# lamloei_node32s3wroom_cp2102_10_4layers.net
KiCad netlist of a schematic drawn in EAGLE
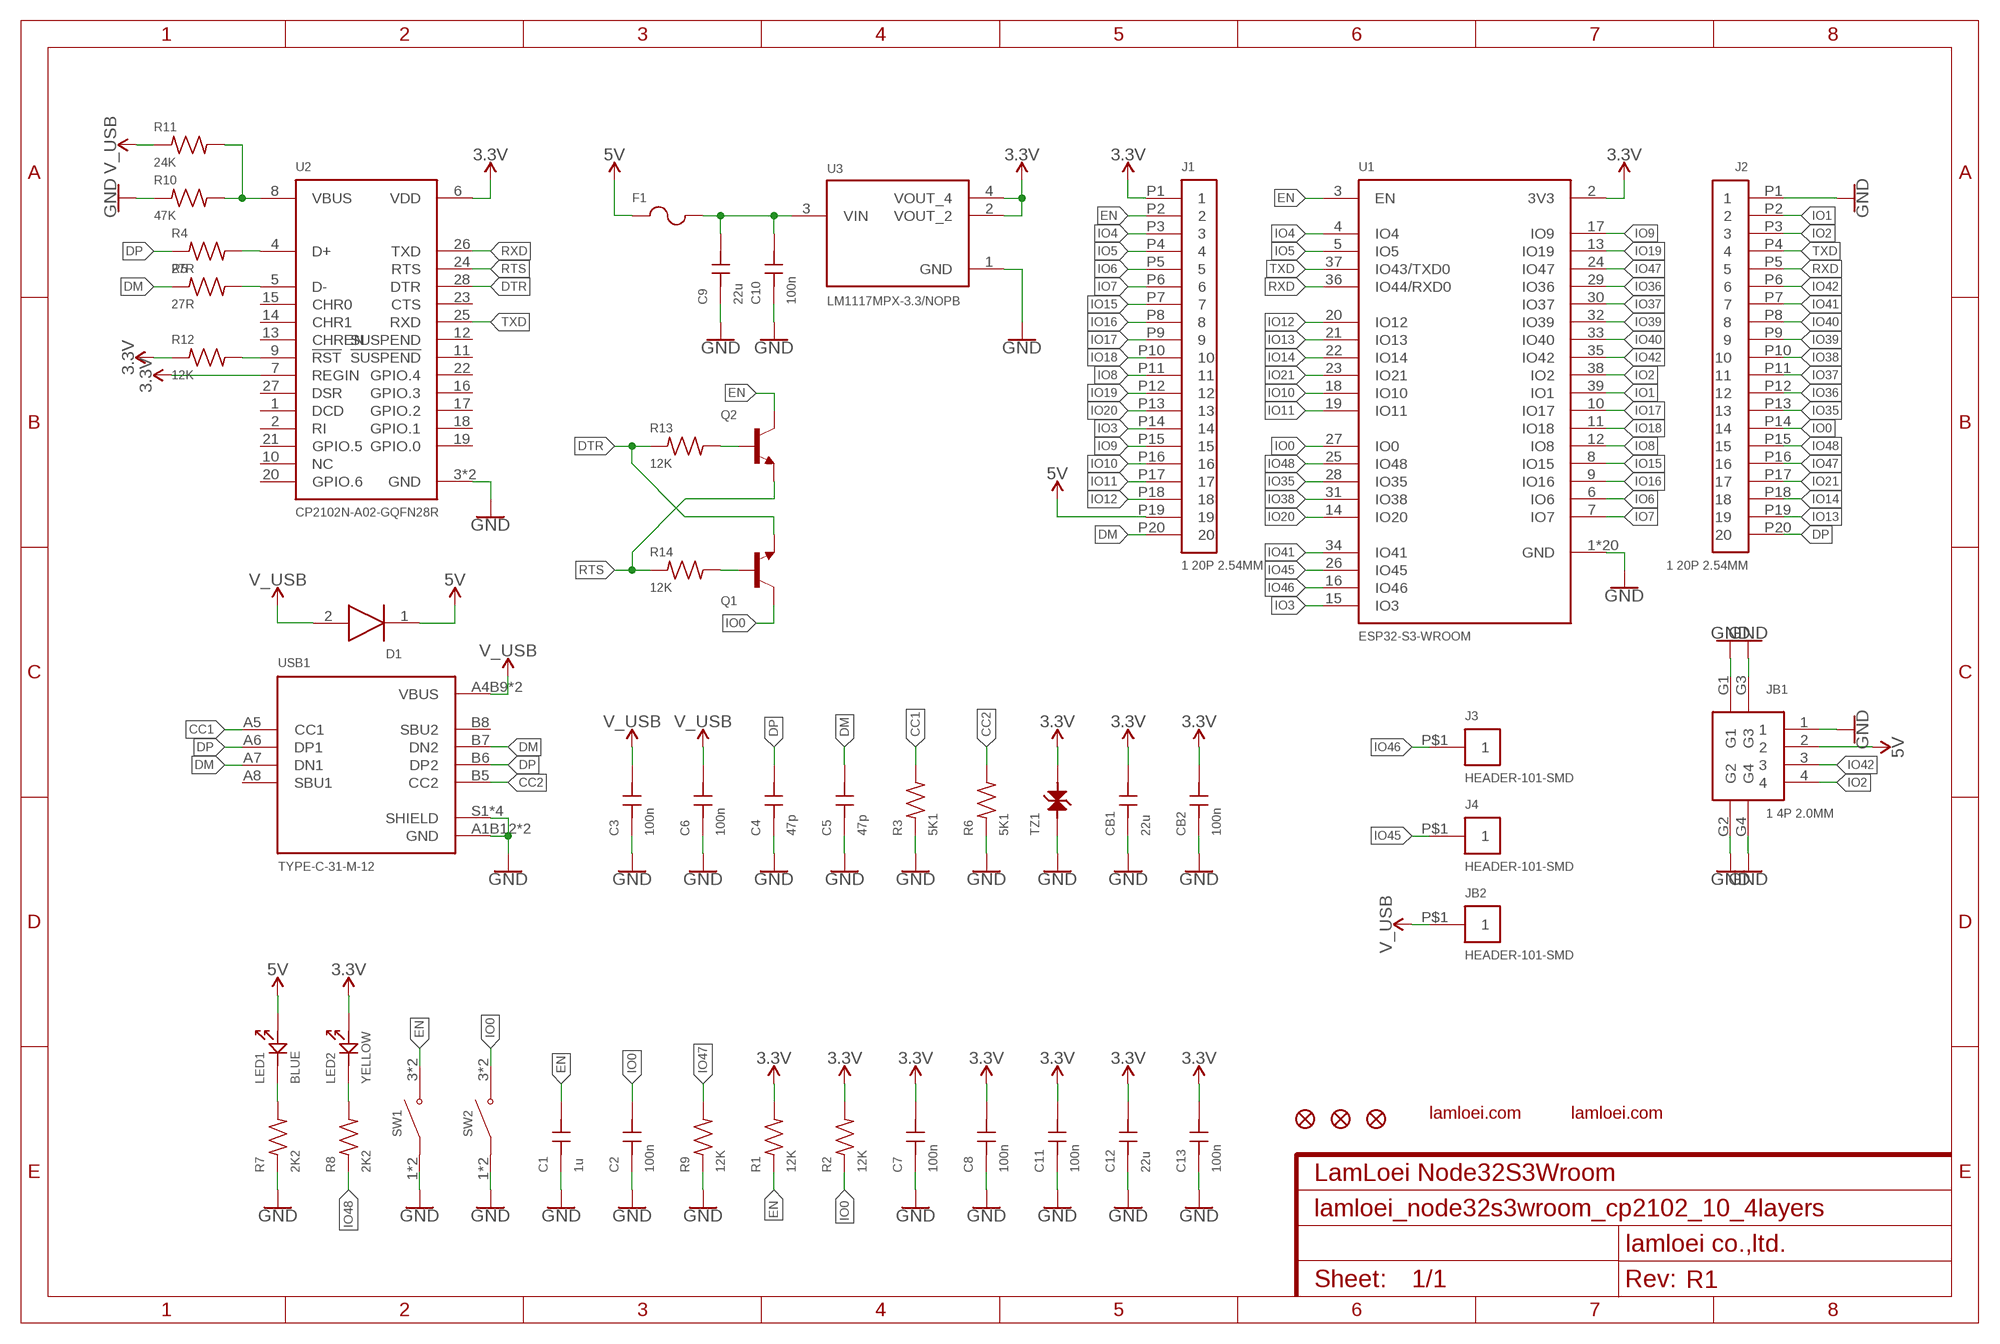
[diagram p0: schematic, sheet 1]

(export (version "E")
  (design (tool "Eeschema 10.0.6"))
  (components
    (comp (ref "C1")
      (value "1u")
      (footprint "eagle-import:GRM155R70J105KA12D")
      (fields (field (name "MANUFACTURER_PART_NUMBER") "GRM155R70J105KA12D"))
      (libsource (lib "eagle-import") (part "GRM155R70J105KA12D"))
    )
    (comp (ref "C2")
      (value "100n")
      (footprint "eagle-import:GCM155R71H104KE02D")
      (fields (field (name "MANUFACTURER_PART_NUMBER") "GCM155R71H104KE02D"))
      (libsource (lib "eagle-import") (part "GCM155R71H104KE02D"))
    )
    (comp (ref "C3")
      (value "100n")
      (footprint "eagle-import:GCM155R71H104KE02D")
      (fields (field (name "MANUFACTURER_PART_NUMBER") "GCM155R71H104KE02D"))
      (libsource (lib "eagle-import") (part "GCM155R71H104KE02D"))
    )
    (comp (ref "C4")
      (value "47p")
      (footprint "eagle-import:GCM1555C1H470JA16D")
      (fields (field (name "MANUFACTURER_PART_NUMBER") "GCM1555C1H470JA16D"))
      (libsource (lib "eagle-import") (part "GCM1555C1H470JA16D"))
    )
    (comp (ref "C5")
      (value "47p")
      (footprint "eagle-import:GCM1555C1H470JA16D")
      (fields (field (name "MANUFACTURER_PART_NUMBER") "GCM1555C1H470JA16D"))
      (libsource (lib "eagle-import") (part "GCM1555C1H470JA16D"))
    )
    (comp (ref "C6")
      (value "100n")
      (footprint "eagle-import:GCM155R71H104KE02D")
      (fields (field (name "MANUFACTURER_PART_NUMBER") "GCM155R71H104KE02D"))
      (libsource (lib "eagle-import") (part "GCM155R71H104KE02D"))
    )
    (comp (ref "C7")
      (value "100n")
      (footprint "eagle-import:GCM155R71H104KE02D")
      (fields (field (name "MANUFACTURER_PART_NUMBER") "GCM155R71H104KE02D"))
      (libsource (lib "eagle-import") (part "GCM155R71H104KE02D"))
    )
    (comp (ref "C8")
      (value "100n")
      (footprint "eagle-import:GCM155R71H104KE02D")
      (fields (field (name "MANUFACTURER_PART_NUMBER") "GCM155R71H104KE02D"))
      (libsource (lib "eagle-import") (part "GCM155R71H104KE02D"))
    )
    (comp (ref "C9")
      (value "22u")
      (footprint "eagle-import:GCM21BR71H105KA03L")
      (fields (field (name "MANUFACTURER_PART_NUMBER") "GCM21BR71H105KA03L"))
      (libsource (lib "eagle-import") (part "GCM21BR71H105KA03L"))
    )
    (comp (ref "C10")
      (value "100n")
      (footprint "eagle-import:GCM155R71H104KE02D")
      (fields (field (name "MANUFACTURER_PART_NUMBER") "GCM155R71H104KE02D"))
      (libsource (lib "eagle-import") (part "GCM155R71H104KE02D"))
    )
    (comp (ref "C11")
      (value "100n")
      (footprint "eagle-import:GCM155R71H104KE02D")
      (fields (field (name "MANUFACTURER_PART_NUMBER") "GCM155R71H104KE02D"))
      (libsource (lib "eagle-import") (part "GCM155R71H104KE02D"))
    )
    (comp (ref "C12")
      (value "22u")
      (footprint "eagle-import:GCM21BR71H105KA03L")
      (fields (field (name "MANUFACTURER_PART_NUMBER") "GCM21BR71H105KA03L"))
      (libsource (lib "eagle-import") (part "GCM21BR71H105KA03L"))
    )
    (comp (ref "C13")
      (value "100n")
      (footprint "eagle-import:GCM155R71H104KE02D")
      (fields (field (name "MANUFACTURER_PART_NUMBER") "GCM155R71H104KE02D"))
      (libsource (lib "eagle-import") (part "GCM155R71H104KE02D"))
    )
    (comp (ref "CB1")
      (value "22u")
      (footprint "eagle-import:GCM21BR71H105KA03L")
      (fields (field (name "MANUFACTURER_PART_NUMBER") "GCM21BR71H105KA03L"))
      (libsource (lib "eagle-import") (part "GCM21BR71H105KA03L"))
    )
    (comp (ref "CB2")
      (value "100n")
      (footprint "eagle-import:GCM155R71H104KE02D")
      (fields (field (name "MANUFACTURER_PART_NUMBER") "GCM155R71H104KE02D"))
      (libsource (lib "eagle-import") (part "GCM155R71H104KE02D"))
    )
    (comp (ref "D1")
      (value "PMEG4050EP,115")
      (footprint "eagle-import:PMEG4050EP,115")
      (fields (field (name "RS_PART_NUMBER") "7805405P"))
      (libsource (lib "eagle-import") (part "PMEG4050EP,115"))
    )
    (comp (ref "F1")
      (value "MF-NSMF050-2")
      (footprint "eagle-import:MF-NSMF050-2")
      (fields (field (name "LCSC_PART") "C75464") (field (name "MANUFACTURER") "BOURNS"))
      (libsource (lib "eagle-import") (part "MF-NSMF050-2"))
    )
    (comp (ref "J1")
      (value "1 20P 2.54MM")
      (footprint "eagle-import:HEADER-120")
      (libsource (lib "eagle-import") (part "HEADER-120"))
    )
    (comp (ref "J2")
      (value "1 20P 2.54MM")
      (footprint "eagle-import:HEADER-120")
      (libsource (lib "eagle-import") (part "lamloei_e77_HEADER-120B_HEADER-120"))
    )
    (comp (ref "J3")
      (value "HEADER-101-SMD")
      (footprint "eagle-import:HEADER-101-SMD")
      (libsource (lib "eagle-import") (part "HEADER-101-SMD"))
    )
    (comp (ref "J4")
      (value "HEADER-101-SMD")
      (footprint "eagle-import:HEADER-101-SMD")
      (libsource (lib "eagle-import") (part "HEADER-101-SMD"))
    )
    (comp (ref "JB1")
      (value "1 4P 2.0MM")
      (footprint "eagle-import:A2012WR-S-4P")
      (libsource (lib "eagle-import") (part "A2012WR-S-4P"))
    )
    (comp (ref "JB2")
      (value "HEADER-101-SMD")
      (footprint "eagle-import:HEADER-101-SMD")
      (libsource (lib "eagle-import") (part "HEADER-101-SMD"))
    )
    (comp (ref "LED1")
      (value "BLUE")
      (footprint "eagle-import:19-217BHC-ZL1M2RY3T")
      (fields (field (name "MANUFACTURER_PART_NUMBER") "19-217BHC-ZL1M2RY3T"))
      (libsource (lib "eagle-import") (part "19-217BHC-ZL1M2RY3T"))
    )
    (comp (ref "LED2")
      (value "YELLOW")
      (footprint "eagle-import:19-213_Y2C-CQ2R2L_3T(CY)")
      (fields (field (name "MANUFACTURER_PART_NUMBER") "19-213/Y2C-CQ2R2L/3T(CY)"))
      (libsource (lib "eagle-import") (part "19-213/Y2C-CQ2R2L/3T(CY)"))
    )
    (comp (ref "Q1")
      (value "BC847B,215")
      (footprint "eagle-import:BC847B,215")
      (fields (field (name "MF") "ON Semiconductor") (field (name "MP") "BC847BLT3G"))
      (libsource (lib "eagle-import") (part "BC847B,215"))
    )
    (comp (ref "Q2")
      (value "BC847B,215")
      (footprint "eagle-import:BC847B,215")
      (fields (field (name "MF") "ON Semiconductor") (field (name "MP") "BC847BLT3G"))
      (libsource (lib "eagle-import") (part "BC847B,215"))
    )
    (comp (ref "R1")
      (value "12K")
      (footprint "eagle-import:R0402")
      (fields
        (field (name "LCSC_PART") "C114760")
        (field (name "MANUFACTURER") "YAGEO")
        (field (name "MANUFACTURER_PART_NUMBER") "RC0402FR-0712KL")
      )
      (libsource (lib "eagle-import") (part "RC0402FR-0712KL"))
    )
    (comp (ref "R2")
      (value "12K")
      (footprint "eagle-import:R0402")
      (fields
        (field (name "LCSC_PART") "C114760")
        (field (name "MANUFACTURER") "YAGEO")
        (field (name "MANUFACTURER_PART_NUMBER") "RC0402FR-0712KL")
      )
      (libsource (lib "eagle-import") (part "RC0402FR-0712KL"))
    )
    (comp (ref "R3")
      (value "5K1")
      (footprint "eagle-import:R0402")
      (fields
        (field (name "LCSC_PART") "C105872")
        (field (name "MANUFACTURER") "YAGEO")
        (field (name "MANUFACTURER_PART_NUMBER") "RC0402FR-075K1L")
      )
      (libsource (lib "eagle-import") (part "RC0402FR-075K1L"))
    )
    (comp (ref "R4")
      (value "27R")
      (footprint "eagle-import:R0402")
      (fields
        (field (name "LCSC_PART") "C138021")
        (field (name "MANUFACTURER") "YAGEO")
        (field (name "MANUFACTURER_PART_NUMBER") "RC0402FR-0727RL")
      )
      (libsource (lib "eagle-import") (part "RC0402FR-0727RL"))
    )
    (comp (ref "R5")
      (value "27R")
      (footprint "eagle-import:R0402")
      (fields
        (field (name "LCSC_PART") "C138021")
        (field (name "MANUFACTURER") "YAGEO")
        (field (name "MANUFACTURER_PART_NUMBER") "RC0402FR-0727RL")
      )
      (libsource (lib "eagle-import") (part "RC0402FR-0727RL"))
    )
    (comp (ref "R6")
      (value "5K1")
      (footprint "eagle-import:R0402")
      (fields
        (field (name "LCSC_PART") "C105872")
        (field (name "MANUFACTURER") "YAGEO")
        (field (name "MANUFACTURER_PART_NUMBER") "RC0402FR-075K1L")
      )
      (libsource (lib "eagle-import") (part "RC0402FR-075K1L"))
    )
    (comp (ref "R7")
      (value "2K2")
      (footprint "eagle-import:R0402")
      (fields
        (field (name "LCSC_PART") "C114762")
        (field (name "MANUFACTURER") "YAGEO")
        (field (name "MANUFACTURER_PART_NUMBER") "RC0402FR-072K2L")
      )
      (libsource (lib "eagle-import") (part "RC0402FR-072K2L"))
    )
    (comp (ref "R8")
      (value "2K2")
      (footprint "eagle-import:R0402")
      (fields
        (field (name "LCSC_PART") "C114762")
        (field (name "MANUFACTURER") "YAGEO")
        (field (name "MANUFACTURER_PART_NUMBER") "RC0402FR-072K2L")
      )
      (libsource (lib "eagle-import") (part "RC0402FR-072K2L"))
    )
    (comp (ref "R9")
      (value "12K")
      (footprint "eagle-import:R0402")
      (fields
        (field (name "LCSC_PART") "C114760")
        (field (name "MANUFACTURER") "YAGEO")
        (field (name "MANUFACTURER_PART_NUMBER") "RC0402FR-0712KL")
      )
      (libsource (lib "eagle-import") (part "RC0402FR-0712KL"))
    )
    (comp (ref "R10")
      (value "47K")
      (footprint "eagle-import:R0402")
      (fields
        (field (name "LCSC_PART") "C93943")
        (field (name "MANUFACTURER") "YAGEO")
        (field (name "MANUFACTURER_PART_NUMBER") "RC0402FR-0747KL")
      )
      (libsource (lib "eagle-import") (part "RC0402FR-0747KL"))
    )
    (comp (ref "R11")
      (value "24K")
      (footprint "eagle-import:R0402")
      (fields
        (field (name "LCSC_PART") "C138026")
        (field (name "MANUFACTURER") "YAGEO")
        (field (name "MANUFACTURER_PART_NUMBER") "RC0402FR-0724KL")
      )
      (libsource (lib "eagle-import") (part "RC0402FR-0724KL"))
    )
    (comp (ref "R12")
      (value "12K")
      (footprint "eagle-import:R0402")
      (fields
        (field (name "LCSC_PART") "C114760")
        (field (name "MANUFACTURER") "YAGEO")
        (field (name "MANUFACTURER_PART_NUMBER") "RC0402FR-0712KL")
      )
      (libsource (lib "eagle-import") (part "RC0402FR-0712KL"))
    )
    (comp (ref "R13")
      (value "12K")
      (footprint "eagle-import:R0402")
      (fields
        (field (name "LCSC_PART") "C114760")
        (field (name "MANUFACTURER") "YAGEO")
        (field (name "MANUFACTURER_PART_NUMBER") "RC0402FR-0712KL")
      )
      (libsource (lib "eagle-import") (part "RC0402FR-0712KL"))
    )
    (comp (ref "R14")
      (value "12K")
      (footprint "eagle-import:R0402")
      (fields
        (field (name "LCSC_PART") "C114760")
        (field (name "MANUFACTURER") "YAGEO")
        (field (name "MANUFACTURER_PART_NUMBER") "RC0402FR-0712KL")
      )
      (libsource (lib "eagle-import") (part "RC0402FR-0712KL"))
    )
    (comp (ref "SW1")
      (value "K2-1808SN-A4SW-01")
      (footprint "eagle-import:K2-1808SN-A4SW-01")
      (fields (field (name "COMMENT") "4-1437565-2") (field (name "MF") "TE Connectivity"))
      (libsource (lib "eagle-import") (part "K2-1808SN-A4SW-01"))
    )
    (comp (ref "SW2")
      (value "K2-1808SN-A4SW-01")
      (footprint "eagle-import:K2-1808SN-A4SW-01")
      (fields (field (name "COMMENT") "4-1437565-2") (field (name "MF") "TE Connectivity"))
      (libsource (lib "eagle-import") (part "K2-1808SN-A4SW-01"))
    )
    (comp (ref "TZ1")
      (value "LXES15AAA1-153")
      (footprint "eagle-import:LXES15AAA1-153")
      (fields (field (name "LCSC_PART") "C86141") (field (name "MANUFACTURER") "Murata"))
      (libsource (lib "eagle-import") (part "LXES15AAA1-153"))
    )
    (comp (ref "U1")
      (value "ESP32-S3-WROOM")
      (footprint "eagle-import:ESP32-S3-WROOM")
      (fields (field (name "MF") "Olimex LTD") (field (name "MP") "ESP-WROOM-32"))
      (libsource (lib "eagle-import") (part "ESP32-S3-WROOM"))
    )
    (comp (ref "U2")
      (value "CP2102N-A02-GQFN28R")
      (footprint "eagle-import:CP2102N-A02-GQFN28R")
      (libsource (lib "eagle-import") (part "CP2102N-A02-GQFN28R"))
    )
    (comp (ref "U3")
      (value "LM1117MPX-3.3/NOPB")
      (footprint "eagle-import:LM1117MPX-3.3_NOPB")
      (fields (field (name "MF") "Texas Instruments"))
      (libsource (lib "eagle-import") (part "LM1117MPX-3.3/NOPB"))
    )
    (comp (ref "USB1")
      (value "TYPE-C-31-M-12")
      (footprint "eagle-import:TYPE-C-31-M-12")
      (fields (field (name "MF") "HRO Electronics Co., Ltd."))
      (libsource (lib "eagle-import") (part "TYPE-C-31-M-12"))
    )
    (comp (ref "ZFD1")
      (value "FIDUCIAL1X2")
      (footprint "eagle-import:FIDUCIAL-1X2")
      (libsource (lib "eagle-import") (part "FIDUCIAL1X2"))
    )
    (comp (ref "ZFD2")
      (value "FIDUCIAL1X2")
      (footprint "eagle-import:FIDUCIAL-1X2")
      (libsource (lib "eagle-import") (part "FIDUCIAL1X2"))
    )
    (comp (ref "ZFD3")
      (value "FIDUCIAL1X2")
      (footprint "eagle-import:FIDUCIAL-1X2")
      (libsource (lib "eagle-import") (part "FIDUCIAL1X2"))
    )
    (comp (ref "ZL1")
      (value "LAMLEOI_LOGO_3")
      (footprint "eagle-import:LAMLEOI_LOGO_3")
      (libsource (lib "eagle-import") (part "LAMLEOI_LOGO_3"))
    )
    (comp (ref "ZL2")
      (value "LAMLEOI_LOGO_3")
      (footprint "eagle-import:LAMLEOI_LOGO_3")
      (libsource (lib "eagle-import") (part "LAMLEOI_LOGO_3"))
    )
  )
  (nets
    (net (code "1") (name "/GPIO.5") (class "Default")
      (node (ref "U2") (pin "21") (pinfunction "GPIO.5_21") (pintype "power_in"))
    )
    (net (code "2") (name "3.3V") (class "Default")
      (node (ref "C11") (pin "2") (pinfunction "2_2") (pintype "passive"))
      (node (ref "C12") (pin "2") (pinfunction "2_2") (pintype "passive"))
      (node (ref "C13") (pin "2") (pinfunction "2_2") (pintype "passive"))
      (node (ref "C7") (pin "2") (pinfunction "2_2") (pintype "passive"))
      (node (ref "C8") (pin "2") (pinfunction "2_2") (pintype "passive"))
      (node (ref "CB1") (pin "2") (pinfunction "2_2") (pintype "passive"))
      (node (ref "CB2") (pin "2") (pinfunction "2_2") (pintype "passive"))
      (node (ref "J1") (pin "P1") (pinfunction "1_P1") (pintype "passive"))
      (node (ref "LED2") (pin "2") (pinfunction "2_2") (pintype "passive"))
      (node (ref "R1") (pin "2") (pinfunction "2_2") (pintype "passive"))
      (node (ref "R12") (pin "1") (pinfunction "1_1") (pintype "passive"))
      (node (ref "R2") (pin "2") (pinfunction "2_2") (pintype "passive"))
      (node (ref "TZ1") (pin "2") (pinfunction "2_2") (pintype "passive"))
      (node (ref "U1") (pin "2") (pinfunction "3V3_2") (pintype "power_in"))
      (node (ref "U2") (pin "6") (pinfunction "VDD_6") (pintype "power_in"))
      (node (ref "U2") (pin "7") (pinfunction "REGIN_7") (pintype "input"))
      (node (ref "U3") (pin "2") (pinfunction "VOUT_2_2") (pintype "output"))
      (node (ref "U3") (pin "4") (pinfunction "VOUT_4_4") (pintype "output"))
    )
    (net (code "3") (name "5V") (class "Default")
      (node (ref "D1") (pin "1") (pinfunction "K_1") (pintype "bidirectional"))
      (node (ref "F1") (pin "1") (pinfunction "1_1") (pintype "passive"))
      (node (ref "J1") (pin "P19") (pinfunction "19_P19") (pintype "passive"))
      (node (ref "JB1") (pin "2") (pinfunction "2_2") (pintype "bidirectional"))
      (node (ref "LED1") (pin "2") (pinfunction "2_2") (pintype "passive"))
    )
    (net (code "4") (name "CC1") (class "Default")
      (node (ref "R3") (pin "2") (pinfunction "2_2") (pintype "passive"))
      (node (ref "USB1") (pin "A5") (pinfunction "CC1_A5") (pintype "bidirectional"))
    )
    (net (code "5") (name "CC2") (class "Default")
      (node (ref "R6") (pin "2") (pinfunction "2_2") (pintype "passive"))
      (node (ref "USB1") (pin "B5") (pinfunction "CC2_B5") (pintype "bidirectional"))
    )
    (net (code "6") (name "DM") (class "Default")
      (node (ref "C5") (pin "2") (pinfunction "2_2") (pintype "passive"))
      (node (ref "J1") (pin "P20") (pinfunction "20_P20") (pintype "passive"))
      (node (ref "R5") (pin "1") (pinfunction "1_1") (pintype "passive"))
      (node (ref "USB1") (pin "A7") (pinfunction "DN1_A7") (pintype "bidirectional"))
      (node (ref "USB1") (pin "B7") (pinfunction "DN2_B7") (pintype "bidirectional"))
    )
    (net (code "7") (name "DP") (class "Default")
      (node (ref "C4") (pin "2") (pinfunction "2_2") (pintype "passive"))
      (node (ref "J2") (pin "P20") (pinfunction "20_P20") (pintype "passive"))
      (node (ref "R4") (pin "1") (pinfunction "1_1") (pintype "passive"))
      (node (ref "USB1") (pin "A6") (pinfunction "DP1_A6") (pintype "bidirectional"))
      (node (ref "USB1") (pin "B6") (pinfunction "DP2_B6") (pintype "bidirectional"))
    )
    (net (code "8") (name "DTR") (class "Default")
      (node (ref "Q1") (pin "E") (pinfunction "E_E") (pintype "passive"))
      (node (ref "R13") (pin "1") (pinfunction "1_1") (pintype "passive"))
      (node (ref "U2") (pin "28") (pinfunction "DTR_28") (pintype "output"))
    )
    (net (code "9") (name "EN") (class "Default")
      (node (ref "C1") (pin "2") (pinfunction "2_2") (pintype "passive"))
      (node (ref "J1") (pin "P2") (pinfunction "2_P2") (pintype "passive"))
      (node (ref "Q2") (pin "C") (pinfunction "C_C") (pintype "passive"))
      (node (ref "R1") (pin "1") (pinfunction "1_1") (pintype "passive"))
      (node (ref "SW1") (pin "3") (pinfunction "NO_3") (pintype "passive"))
      (node (ref "SW1") (pin "4") (pinfunction "NO_4") (pintype "passive"))
      (node (ref "U1") (pin "3") (pinfunction "EN_3") (pintype "input"))
    )
    (net (code "10") (name "GND") (class "Default")
      (node (ref "C1") (pin "1") (pinfunction "1_1") (pintype "passive"))
      (node (ref "C10") (pin "1") (pinfunction "1_1") (pintype "passive"))
      (node (ref "C11") (pin "1") (pinfunction "1_1") (pintype "passive"))
      (node (ref "C12") (pin "1") (pinfunction "1_1") (pintype "passive"))
      (node (ref "C13") (pin "1") (pinfunction "1_1") (pintype "passive"))
      (node (ref "C2") (pin "1") (pinfunction "1_1") (pintype "passive"))
      (node (ref "C3") (pin "1") (pinfunction "1_1") (pintype "passive"))
      (node (ref "C4") (pin "1") (pinfunction "1_1") (pintype "passive"))
      (node (ref "C5") (pin "1") (pinfunction "1_1") (pintype "passive"))
      (node (ref "C6") (pin "1") (pinfunction "1_1") (pintype "passive"))
      (node (ref "C7") (pin "1") (pinfunction "1_1") (pintype "passive"))
      (node (ref "C8") (pin "1") (pinfunction "1_1") (pintype "passive"))
      (node (ref "C9") (pin "1") (pinfunction "1_1") (pintype "passive"))
      (node (ref "CB1") (pin "1") (pinfunction "1_1") (pintype "passive"))
      (node (ref "CB2") (pin "1") (pinfunction "1_1") (pintype "passive"))
      (node (ref "J2") (pin "P1") (pinfunction "1_P1") (pintype "passive"))
      (node (ref "JB1") (pin "1") (pinfunction "1_1") (pintype "bidirectional"))
      (node (ref "JB1") (pin "G1") (pinfunction "G1_G1") (pintype "bidirectional"))
      (node (ref "JB1") (pin "G2") (pinfunction "G2_G2") (pintype "bidirectional"))
      (node (ref "JB1") (pin "G3") (pinfunction "G3_G3") (pintype "bidirectional"))
      (node (ref "JB1") (pin "G4") (pinfunction "G4_G4") (pintype "bidirectional"))
      (node (ref "R10") (pin "1") (pinfunction "1_1") (pintype "passive"))
      (node (ref "R3") (pin "1") (pinfunction "1_1") (pintype "passive"))
      (node (ref "R6") (pin "1") (pinfunction "1_1") (pintype "passive"))
      (node (ref "R7") (pin "1") (pinfunction "1_1") (pintype "passive"))
      (node (ref "R9") (pin "1") (pinfunction "1_1") (pintype "passive"))
      (node (ref "SW1") (pin "1") (pinfunction "COM_1") (pintype "passive"))
      (node (ref "SW1") (pin "2") (pinfunction "COM_2") (pintype "passive"))
      (node (ref "SW2") (pin "1") (pinfunction "COM_1") (pintype "passive"))
      (node (ref "SW2") (pin "2") (pinfunction "COM_2") (pintype "passive"))
      (node (ref "TZ1") (pin "1") (pinfunction "1_1") (pintype "passive"))
      (node (ref "U1") (pin "1") (pinfunction "GND_1") (pintype "power_in"))
      (node (ref "U1") (pin "1.1") (pinfunction "GND_1.1") (pintype "power_in"))
      (node (ref "U1") (pin "1.10") (pinfunction "GND_1.10") (pintype "power_in"))
      (node (ref "U1") (pin "1.11") (pinfunction "GND_1.11") (pintype "power_in"))
      (node (ref "U1") (pin "1.12") (pinfunction "GND_1.12") (pintype "power_in"))
      (node (ref "U1") (pin "1.13") (pinfunction "GND_1.13") (pintype "power_in"))
      (node (ref "U1") (pin "1.14") (pinfunction "GND_1.14") (pintype "power_in"))
      (node (ref "U1") (pin "1.15") (pinfunction "GND_1.15") (pintype "power_in"))
      (node (ref "U1") (pin "1.16") (pinfunction "GND_1.16") (pintype "power_in"))
      (node (ref "U1") (pin "1.17") (pinfunction "GND_1.17") (pintype "power_in"))
      (node (ref "U1") (pin "1.18") (pinfunction "GND_1.18") (pintype "power_in"))
      (node (ref "U1") (pin "1.2") (pinfunction "GND_1.2") (pintype "power_in"))
      (node (ref "U1") (pin "1.3") (pinfunction "GND_1.3") (pintype "power_in"))
      (node (ref "U1") (pin "1.4") (pinfunction "GND_1.4") (pintype "power_in"))
      (node (ref "U1") (pin "1.5") (pinfunction "GND_1.5") (pintype "power_in"))
      (node (ref "U1") (pin "1.6") (pinfunction "GND_1.6") (pintype "power_in"))
      (node (ref "U1") (pin "1.7") (pinfunction "GND_1.7") (pintype "power_in"))
      (node (ref "U1") (pin "1.8") (pinfunction "GND_1.8") (pintype "power_in"))
      (node (ref "U1") (pin "1.9") (pinfunction "GND_1.9") (pintype "power_in"))
      (node (ref "U1") (pin "40") (pinfunction "GND_40") (pintype "power_in"))
      (node (ref "U2") (pin "29") (pinfunction "GND_29") (pintype "power_in"))
      (node (ref "U2") (pin "3") (pinfunction "GND_3") (pintype "power_in"))
      (node (ref "U3") (pin "1") (pinfunction "GND_1") (pintype "power_in"))
      (node (ref "USB1") (pin "A1B12") (pinfunction "GND_A1B12") (pintype "power_in"))
      (node (ref "USB1") (pin "B1A12") (pinfunction "GND_B1A12") (pintype "power_in"))
      (node (ref "USB1") (pin "S1") (pinfunction "SHIELD_S1") (pintype "passive"))
      (node (ref "USB1") (pin "S2") (pinfunction "SHIELD_S2") (pintype "passive"))
      (node (ref "USB1") (pin "S3") (pinfunction "SHIELD_S3") (pintype "passive"))
      (node (ref "USB1") (pin "S4") (pinfunction "SHIELD_S4") (pintype "passive"))
    )
    (net (code "11") (name "IO0") (class "Default")
      (node (ref "C2") (pin "2") (pinfunction "2_2") (pintype "passive"))
      (node (ref "J2") (pin "P14") (pinfunction "14_P14") (pintype "passive"))
      (node (ref "Q1") (pin "C") (pinfunction "C_C") (pintype "passive"))
      (node (ref "R2") (pin "1") (pinfunction "1_1") (pintype "passive"))
      (node (ref "SW2") (pin "3") (pinfunction "NO_3") (pintype "passive"))
      (node (ref "SW2") (pin "4") (pinfunction "NO_4") (pintype "passive"))
      (node (ref "U1") (pin "27") (pinfunction "IO0_27") (pintype "bidirectional"))
    )
    (net (code "12") (name "IO1") (class "Default")
      (node (ref "J2") (pin "P2") (pinfunction "2_P2") (pintype "passive"))
      (node (ref "U1") (pin "39") (pinfunction "IO1_39") (pintype "bidirectional"))
    )
    (net (code "13") (name "IO2") (class "Default")
      (node (ref "J2") (pin "P3") (pinfunction "3_P3") (pintype "passive"))
      (node (ref "JB1") (pin "4") (pinfunction "4_4") (pintype "bidirectional"))
      (node (ref "U1") (pin "38") (pinfunction "IO2_38") (pintype "bidirectional"))
    )
    (net (code "14") (name "IO3") (class "Default")
      (node (ref "J1") (pin "P14") (pinfunction "14_P14") (pintype "passive"))
      (node (ref "U1") (pin "15") (pinfunction "IO3_15") (pintype "bidirectional"))
    )
    (net (code "15") (name "IO4") (class "Default")
      (node (ref "J1") (pin "P3") (pinfunction "3_P3") (pintype "passive"))
      (node (ref "U1") (pin "4") (pinfunction "IO4_4") (pintype "input"))
    )
    (net (code "16") (name "IO5") (class "Default")
      (node (ref "J1") (pin "P4") (pinfunction "4_P4") (pintype "passive"))
      (node (ref "U1") (pin "5") (pinfunction "IO5_5") (pintype "input"))
    )
    (net (code "17") (name "IO6") (class "Default")
      (node (ref "J1") (pin "P5") (pinfunction "5_P5") (pintype "passive"))
      (node (ref "U1") (pin "6") (pinfunction "IO6_6") (pintype "bidirectional"))
    )
    (net (code "18") (name "IO7") (class "Default")
      (node (ref "J1") (pin "P6") (pinfunction "6_P6") (pintype "passive"))
      (node (ref "U1") (pin "7") (pinfunction "IO7_7") (pintype "bidirectional"))
    )
    (net (code "19") (name "IO8") (class "Default")
      (node (ref "J1") (pin "P11") (pinfunction "11_P11") (pintype "passive"))
      (node (ref "U1") (pin "12") (pinfunction "IO8_12") (pintype "bidirectional"))
    )
    (net (code "20") (name "IO9") (class "Default")
      (node (ref "J1") (pin "P15") (pinfunction "15_P15") (pintype "passive"))
      (node (ref "U1") (pin "17") (pinfunction "IO9_17") (pintype "bidirectional"))
    )
    (net (code "21") (name "IO10") (class "Default")
      (node (ref "J1") (pin "P16") (pinfunction "16_P16") (pintype "passive"))
      (node (ref "U1") (pin "18") (pinfunction "IO10_18") (pintype "bidirectional"))
    )
    (net (code "22") (name "IO11") (class "Default")
      (node (ref "J1") (pin "P17") (pinfunction "17_P17") (pintype "passive"))
      (node (ref "U1") (pin "19") (pinfunction "IO11_19") (pintype "bidirectional"))
    )
    (net (code "23") (name "IO12") (class "Default")
      (node (ref "J1") (pin "P18") (pinfunction "18_P18") (pintype "passive"))
      (node (ref "U1") (pin "20") (pinfunction "IO12_20") (pintype "bidirectional"))
    )
    (net (code "24") (name "IO13") (class "Default")
      (node (ref "J2") (pin "P19") (pinfunction "19_P19") (pintype "passive"))
      (node (ref "U1") (pin "21") (pinfunction "IO13_21") (pintype "bidirectional"))
    )
    (net (code "25") (name "IO14") (class "Default")
      (node (ref "J2") (pin "P18") (pinfunction "18_P18") (pintype "passive"))
      (node (ref "U1") (pin "22") (pinfunction "IO14_22") (pintype "bidirectional"))
    )
    (net (code "26") (name "IO15") (class "Default")
      (node (ref "J1") (pin "P7") (pinfunction "7_P7") (pintype "passive"))
      (node (ref "U1") (pin "8") (pinfunction "IO15_8") (pintype "bidirectional"))
    )
    (net (code "27") (name "IO16") (class "Default")
      (node (ref "J1") (pin "P8") (pinfunction "8_P8") (pintype "passive"))
      (node (ref "U1") (pin "9") (pinfunction "IO16_9") (pintype "bidirectional"))
    )
    (net (code "28") (name "IO17") (class "Default")
      (node (ref "J1") (pin "P9") (pinfunction "9_P9") (pintype "passive"))
      (node (ref "U1") (pin "10") (pinfunction "IO17_10") (pintype "bidirectional"))
    )
    (net (code "29") (name "IO18") (class "Default")
      (node (ref "J1") (pin "P10") (pinfunction "10_P10") (pintype "passive"))
      (node (ref "U1") (pin "11") (pinfunction "IO18_11") (pintype "bidirectional"))
    )
    (net (code "30") (name "IO19") (class "Default")
      (node (ref "J1") (pin "P12") (pinfunction "12_P12") (pintype "passive"))
      (node (ref "U1") (pin "13") (pinfunction "IO19_13") (pintype "bidirectional"))
    )
    (net (code "31") (name "IO20") (class "Default")
      (node (ref "J1") (pin "P13") (pinfunction "13_P13") (pintype "passive"))
      (node (ref "U1") (pin "14") (pinfunction "IO20_14") (pintype "bidirectional"))
    )
    (net (code "32") (name "IO21") (class "Default")
      (node (ref "J2") (pin "P17") (pinfunction "17_P17") (pintype "passive"))
      (node (ref "U1") (pin "23") (pinfunction "IO21_23") (pintype "bidirectional"))
    )
    (net (code "33") (name "IO35") (class "Default")
      (node (ref "J2") (pin "P13") (pinfunction "13_P13") (pintype "passive"))
      (node (ref "U1") (pin "28") (pinfunction "IO35_28") (pintype "bidirectional"))
    )
    (net (code "34") (name "IO36") (class "Default")
      (node (ref "J2") (pin "P12") (pinfunction "12_P12") (pintype "passive"))
      (node (ref "U1") (pin "29") (pinfunction "IO36_29") (pintype "bidirectional"))
    )
    (net (code "35") (name "IO37") (class "Default")
      (node (ref "J2") (pin "P11") (pinfunction "11_P11") (pintype "passive"))
      (node (ref "U1") (pin "30") (pinfunction "IO37_30") (pintype "bidirectional"))
    )
    (net (code "36") (name "IO38") (class "Default")
      (node (ref "J2") (pin "P10") (pinfunction "10_P10") (pintype "passive"))
      (node (ref "U1") (pin "31") (pinfunction "IO38_31") (pintype "bidirectional"))
    )
    (net (code "37") (name "IO39") (class "Default")
      (node (ref "J2") (pin "P9") (pinfunction "9_P9") (pintype "passive"))
      (node (ref "U1") (pin "32") (pinfunction "IO39_32") (pintype "bidirectional"))
    )
    (net (code "38") (name "IO40") (class "Default")
      (node (ref "J2") (pin "P8") (pinfunction "8_P8") (pintype "passive"))
      (node (ref "U1") (pin "33") (pinfunction "IO40_33") (pintype "bidirectional"))
    )
    (net (code "39") (name "IO41") (class "Default")
      (node (ref "J2") (pin "P7") (pinfunction "7_P7") (pintype "passive"))
      (node (ref "U1") (pin "34") (pinfunction "IO41_34") (pintype "bidirectional"))
    )
    (net (code "40") (name "IO42") (class "Default")
      (node (ref "J2") (pin "P6") (pinfunction "6_P6") (pintype "passive"))
      (node (ref "JB1") (pin "3") (pinfunction "3_3") (pintype "bidirectional"))
      (node (ref "U1") (pin "35") (pinfunction "IO42_35") (pintype "bidirectional"))
    )
    (net (code "41") (name "IO45") (class "Default")
      (node (ref "J4") (pin "P$1") (pinfunction "1_P$1") (pintype "passive"))
      (node (ref "U1") (pin "26") (pinfunction "IO45_26") (pintype "bidirectional"))
    )
    (net (code "42") (name "IO46") (class "Default")
      (node (ref "J3") (pin "P$1") (pinfunction "1_P$1") (pintype "passive"))
      (node (ref "U1") (pin "16") (pinfunction "IO46_16") (pintype "bidirectional"))
    )
    (net (code "43") (name "IO47") (class "Default")
      (node (ref "J2") (pin "P16") (pinfunction "16_P16") (pintype "passive"))
      (node (ref "R9") (pin "2") (pinfunction "2_2") (pintype "passive"))
      (node (ref "U1") (pin "24") (pinfunction "IO47_24") (pintype "bidirectional"))
    )
    (net (code "44") (name "IO48") (class "Default")
      (node (ref "J2") (pin "P15") (pinfunction "15_P15") (pintype "passive"))
      (node (ref "R8") (pin "1") (pinfunction "1_1") (pintype "passive"))
      (node (ref "U1") (pin "25") (pinfunction "IO48_25") (pintype "bidirectional"))
    )
    (net (code "45") (name "Net-(LED1-Pad1)") (class "Default")
      (node (ref "LED1") (pin "1") (pinfunction "1_1") (pintype "passive"))
      (node (ref "R7") (pin "2") (pinfunction "2_2") (pintype "passive"))
    )
    (net (code "46") (name "Net-(LED2-Pad1)") (class "Default")
      (node (ref "LED2") (pin "1") (pinfunction "1_1") (pintype "passive"))
      (node (ref "R8") (pin "2") (pinfunction "2_2") (pintype "passive"))
    )
    (net (code "47") (name "Net-(Q1-PadB)") (class "Default")
      (node (ref "Q1") (pin "B") (pinfunction "B_B") (pintype "passive"))
      (node (ref "R14") (pin "2") (pinfunction "2_2") (pintype "passive"))
    )
    (net (code "48") (name "Net-(Q2-PadB)") (class "Default")
      (node (ref "Q2") (pin "B") (pinfunction "B_B") (pintype "passive"))
      (node (ref "R13") (pin "2") (pinfunction "2_2") (pintype "passive"))
    )
    (net (code "49") (name "Net-(U2-D+)") (class "Default")
      (node (ref "R4") (pin "2") (pinfunction "2_2") (pintype "passive"))
      (node (ref "U2") (pin "4") (pinfunction "D+_4") (pintype "bidirectional"))
    )
    (net (code "50") (name "Net-(U2-D-)") (class "Default")
      (node (ref "R5") (pin "2") (pinfunction "2_2") (pintype "passive"))
      (node (ref "U2") (pin "5") (pinfunction "D-_5") (pintype "bidirectional"))
    )
    (net (code "51") (name "Net-(U2-VBUS)") (class "Default")
      (node (ref "R10") (pin "2") (pinfunction "2_2") (pintype "passive"))
      (node (ref "R11") (pin "2") (pinfunction "2_2") (pintype "passive"))
      (node (ref "U2") (pin "8") (pinfunction "VBUS_8") (pintype "input"))
    )
    (net (code "52") (name "Net-(U2-~{RST})") (class "Default")
      (node (ref "R12") (pin "2") (pinfunction "2_2") (pintype "passive"))
      (node (ref "U2") (pin "9") (pinfunction "~{RST}_9") (pintype "input"))
    )
    (net (code "53") (name "Net-(U3-VIN)") (class "Default")
      (node (ref "C10") (pin "2") (pinfunction "2_2") (pintype "passive"))
      (node (ref "C9") (pin "2") (pinfunction "2_2") (pintype "passive"))
      (node (ref "F1") (pin "2") (pinfunction "2_2") (pintype "passive"))
      (node (ref "U3") (pin "3") (pinfunction "VIN_3") (pintype "input"))
    )
    (net (code "54") (name "RTS") (class "Default")
      (node (ref "Q2") (pin "E") (pinfunction "E_E") (pintype "passive"))
      (node (ref "R14") (pin "1") (pinfunction "1_1") (pintype "passive"))
      (node (ref "U2") (pin "24") (pinfunction "RTS_24") (pintype "output"))
    )
    (net (code "55") (name "RXD") (class "Default")
      (node (ref "J2") (pin "P5") (pinfunction "5_P5") (pintype "passive"))
      (node (ref "U1") (pin "36") (pinfunction "IO44/RXD0_36") (pintype "bidirectional"))
      (node (ref "U2") (pin "26") (pinfunction "TXD_26") (pintype "output"))
    )
    (net (code "56") (name "TXD") (class "Default")
      (node (ref "J2") (pin "P4") (pinfunction "4_P4") (pintype "passive"))
      (node (ref "U1") (pin "37") (pinfunction "IO43/TXD0_37") (pintype "bidirectional"))
      (node (ref "U2") (pin "25") (pinfunction "RXD_25") (pintype "input"))
    )
    (net (code "57") (name "V_USB") (class "Default")
      (node (ref "C3") (pin "2") (pinfunction "2_2") (pintype "passive"))
      (node (ref "C6") (pin "2") (pinfunction "2_2") (pintype "passive"))
      (node (ref "D1") (pin "2") (pinfunction "A_2") (pintype "bidirectional"))
      (node (ref "JB2") (pin "P$1") (pinfunction "1_P$1") (pintype "passive"))
      (node (ref "R11") (pin "1") (pinfunction "1_1") (pintype "passive"))
      (node (ref "USB1") (pin "A4B9") (pinfunction "VBUS_A4B9") (pintype "power_in"))
      (node (ref "USB1") (pin "B4A9") (pinfunction "VBUS_B4A9") (pintype "power_in"))
    )
    (net (code "58") (name "unconnected-(U2-CHR0-Pad15)") (class "Default")
      (node (ref "U2") (pin "15") (pinfunction "CHR0_15") (pintype "input"))
    )
    (net (code "59") (name "unconnected-(U2-CHR1-Pad14)") (class "Default")
      (node (ref "U2") (pin "14") (pinfunction "CHR1_14") (pintype "input"))
    )
    (net (code "60") (name "unconnected-(U2-CHREN-Pad13)") (class "Default")
      (node (ref "U2") (pin "13") (pinfunction "CHREN_13") (pintype "input"))
    )
    (net (code "61") (name "unconnected-(U2-CTS-Pad23)") (class "Default")
      (node (ref "U2") (pin "23") (pinfunction "CTS_23") (pintype "input"))
    )
    (net (code "62") (name "unconnected-(U2-DCD-Pad1)") (class "Default")
      (node (ref "U2") (pin "1") (pinfunction "DCD_1") (pintype "input"))
    )
    (net (code "63") (name "unconnected-(U2-DSR-Pad27)") (class "Default")
      (node (ref "U2") (pin "27") (pinfunction "DSR_27") (pintype "input"))
    )
    (net (code "64") (name "unconnected-(U2-GPIO.0-Pad19)") (class "Default")
      (node (ref "U2") (pin "19") (pinfunction "GPIO.0_19") (pintype "bidirectional"))
    )
    (net (code "65") (name "unconnected-(U2-GPIO.1-Pad18)") (class "Default")
      (node (ref "U2") (pin "18") (pinfunction "GPIO.1_18") (pintype "bidirectional"))
    )
    (net (code "66") (name "unconnected-(U2-GPIO.2-Pad17)") (class "Default")
      (node (ref "U2") (pin "17") (pinfunction "GPIO.2_17") (pintype "bidirectional"))
    )
    (net (code "67") (name "unconnected-(U2-GPIO.3-Pad16)") (class "Default")
      (node (ref "U2") (pin "16") (pinfunction "GPIO.3_16") (pintype "bidirectional"))
    )
    (net (code "68") (name "unconnected-(U2-GPIO.4-Pad22)") (class "Default")
      (node (ref "U2") (pin "22") (pinfunction "GPIO.4_22") (pintype "bidirectional"))
    )
    (net (code "69") (name "unconnected-(U2-GPIO.6-Pad20)") (class "Default")
      (node (ref "U2") (pin "20") (pinfunction "GPIO.6_20") (pintype "passive"))
    )
    (net (code "70") (name "unconnected-(U2-NC-Pad10)") (class "Default")
      (node (ref "U2") (pin "10") (pinfunction "NC_10") (pintype "bidirectional"))
    )
    (net (code "71") (name "unconnected-(U2-RI-Pad2)") (class "Default")
      (node (ref "U2") (pin "2") (pinfunction "RI_2") (pintype "input"))
    )
    (net (code "72") (name "unconnected-(U2-SUSPEND-Pad12)") (class "Default")
      (node (ref "U2") (pin "12") (pinfunction "SUSPEND_12") (pintype "output"))
    )
    (net (code "73") (name "unconnected-(U2-~{SUSPEND}-Pad11)") (class "Default")
      (node (ref "U2") (pin "11") (pinfunction "~{SUSPEND}_11") (pintype "output"))
    )
    (net (code "74") (name "unconnected-(USB1-SBU1-PadA8)") (class "Default")
      (node (ref "USB1") (pin "A8") (pinfunction "SBU1_A8") (pintype "bidirectional"))
    )
    (net (code "75") (name "unconnected-(USB1-SBU2-PadB8)") (class "Default")
      (node (ref "USB1") (pin "B8") (pinfunction "SBU2_B8") (pintype "bidirectional"))
    )
  )
)
